# MCU.net
KiCad netlist of a schematic drawn in Altium Designer
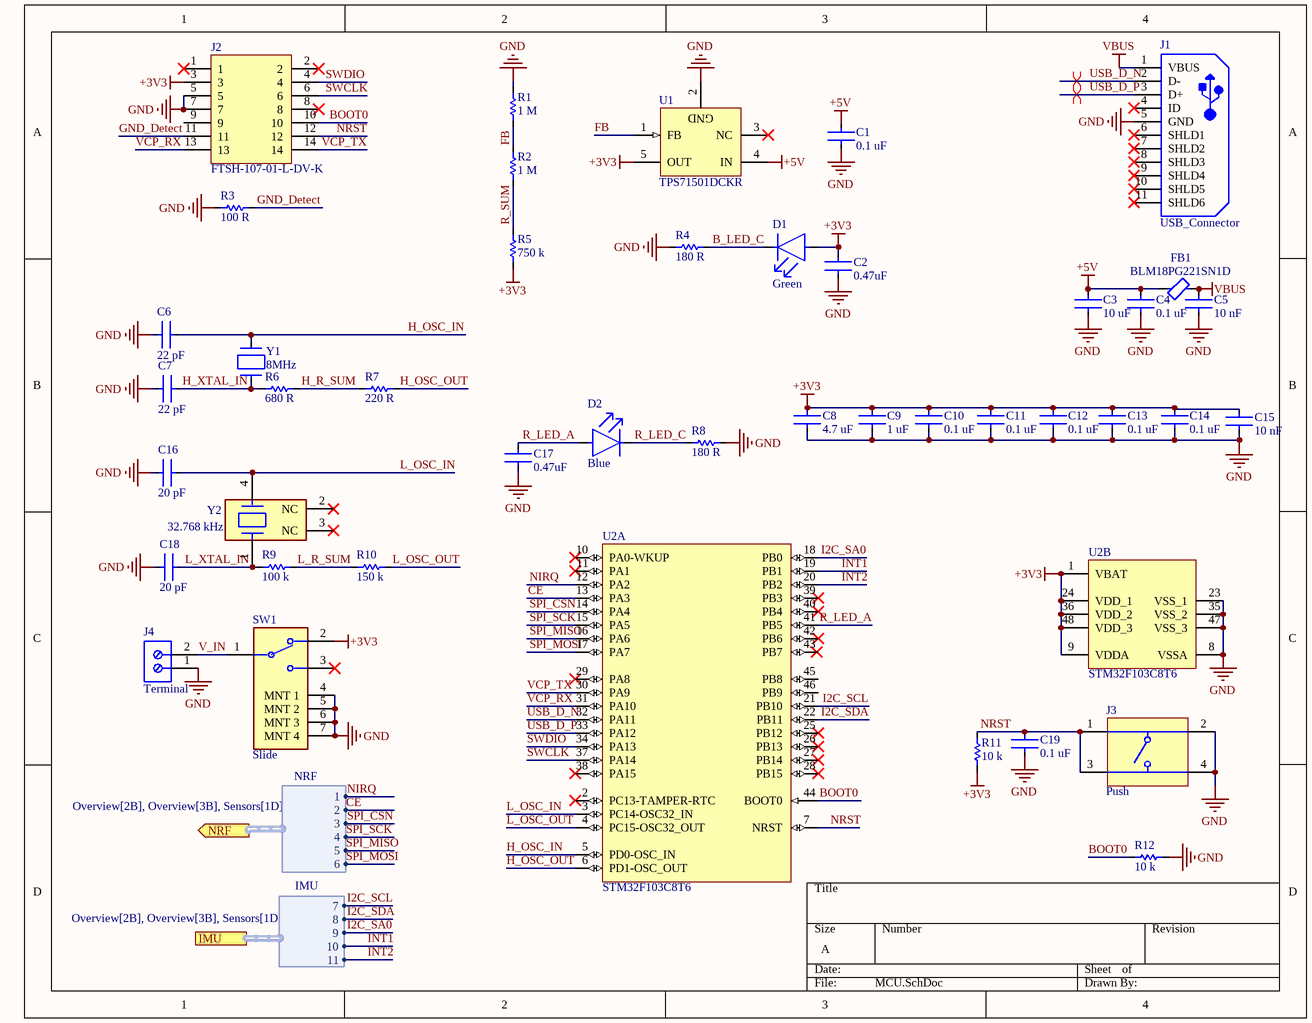
[diagram p0: MCU.SchDoc]

(export (version "E")
  (design (tool "Eeschema 10.0.6"))
  (components
    (comp (ref "C1")
      (value "0.1 uF")
      (footprint "0_1uF_0603_Capacitor")
      (fields
        (field (name "MANUFACTURER") "Murata")
        (field (name "MANUFACTURER PART NUMBER") "GCM188L81H104KA57D")
      )
      (libsource (lib "V2SchLib") (part "0_1uF_0603_Capacitor"))
    )
    (comp (ref "C2")
      (value "0.47uF")
      (footprint "0_47uF_0603_Capacitor")
      (fields
        (field (name "MANUFACTURER") "Murata")
        (field (name "MANUFACTURER PART NUMBER") "GRM188R71E474KA12D")
      )
      (libsource (lib "V2SchLib") (part "0_47uF_0603_Capacitor"))
    )
    (comp (ref "C3")
      (value "10 uF")
      (footprint "10uF_0603_Capacitor")
      (fields
        (field (name "MANUFACTURER") "Murata")
        (field (name "MANUFACTURER PART NUMBER") "GRM188R60J106KE47D")
      )
      (libsource (lib "V2SchLib") (part "10uF_0603_Capacitor"))
    )
    (comp (ref "C4")
      (value "0.1 uF")
      (footprint "0_1uF_0603_Capacitor")
      (fields
        (field (name "MANUFACTURER") "Murata")
        (field (name "MANUFACTURER PART NUMBER") "GCM188L81H104KA57D")
      )
      (libsource (lib "V2SchLib") (part "0_1uF_0603_Capacitor"))
    )
    (comp (ref "C5")
      (value "10 nF")
      (footprint "10nF_0603_Capacitor")
      (fields
        (field (name "MANUFACTURER") "Yageo")
        (field (name "MANUFACTURER PART NUMBER") "CC0603KRX7R9BB103")
      )
      (libsource (lib "V2SchLib") (part "10nF_0603_Capacitor"))
    )
    (comp (ref "C6")
      (value "22 pF")
      (footprint "22pF_0603_Capacitor")
      (fields
        (field (name "MANUFACTURER") "Murata")
        (field (name "MANUFACTURER PART NUMBER") "GCM1885C2A220JA16D")
      )
      (libsource (lib "V2SchLib") (part "22pF_0603_Capacitor"))
    )
    (comp (ref "C7")
      (value "22 pF")
      (footprint "22pF_0603_Capacitor")
      (fields
        (field (name "MANUFACTURER") "Murata")
        (field (name "MANUFACTURER PART NUMBER") "GCM1885C2A220JA16D")
      )
      (libsource (lib "V2SchLib") (part "22pF_0603_Capacitor"))
    )
    (comp (ref "C8")
      (value "4.7 uF")
      (footprint "4_7uF_0603_Capacitor")
      (fields
        (field (name "MANUFACTURER") "Murata")
        (field (name "MANUFACTURER PART NUMBER") "GRM188R61C475KAAJD")
      )
      (libsource (lib "V2SchLib") (part "4_7uF_0603_Capacitor"))
    )
    (comp (ref "C9")
      (value "1 uF")
      (footprint "1uF_0603_Capacitor")
      (fields
        (field (name "MANUFACTURER") "Yageo")
        (field (name "MANUFACTURER PART NUMBER") "CC0603KRX5R9BB105")
      )
      (libsource (lib "V2SchLib") (part "1uF_0603_Capacitor"))
    )
    (comp (ref "C10")
      (value "0.1 uF")
      (footprint "0_1uF_0603_Capacitor")
      (fields
        (field (name "MANUFACTURER") "Murata")
        (field (name "MANUFACTURER PART NUMBER") "GCM188L81H104KA57D")
      )
      (libsource (lib "V2SchLib") (part "0_1uF_0603_Capacitor"))
    )
    (comp (ref "C11")
      (value "0.1 uF")
      (footprint "0_1uF_0603_Capacitor")
      (fields
        (field (name "MANUFACTURER") "Murata")
        (field (name "MANUFACTURER PART NUMBER") "GCM188L81H104KA57D")
      )
      (libsource (lib "V2SchLib") (part "0_1uF_0603_Capacitor"))
    )
    (comp (ref "C12")
      (value "0.1 uF")
      (footprint "0_1uF_0603_Capacitor")
      (fields
        (field (name "MANUFACTURER") "Murata")
        (field (name "MANUFACTURER PART NUMBER") "GCM188L81H104KA57D")
      )
      (libsource (lib "V2SchLib") (part "0_1uF_0603_Capacitor"))
    )
    (comp (ref "C13")
      (value "0.1 uF")
      (footprint "0_1uF_0603_Capacitor")
      (fields
        (field (name "MANUFACTURER") "Murata")
        (field (name "MANUFACTURER PART NUMBER") "GCM188L81H104KA57D")
      )
      (libsource (lib "V2SchLib") (part "0_1uF_0603_Capacitor"))
    )
    (comp (ref "C14")
      (value "0.1 uF")
      (footprint "0_1uF_0603_Capacitor")
      (fields
        (field (name "MANUFACTURER") "Murata")
        (field (name "MANUFACTURER PART NUMBER") "GCM188L81H104KA57D")
      )
      (libsource (lib "V2SchLib") (part "0_1uF_0603_Capacitor"))
    )
    (comp (ref "C15")
      (value "10 nF")
      (footprint "10nF_0603_Capacitor")
      (fields
        (field (name "MANUFACTURER") "Yageo")
        (field (name "MANUFACTURER PART NUMBER") "CC0603KRX7R9BB103")
      )
      (libsource (lib "V2SchLib") (part "10nF_0603_Capacitor"))
    )
    (comp (ref "C16")
      (value "20 pF")
      (footprint "20pF_0603_Capacitor")
      (fields
        (field (name "MANUFACTURER") "Yageo")
        (field (name "MANUFACTURER PART NUMBER") "CC0603JRNPO9BN200")
      )
      (libsource (lib "V2SchLib") (part "20pF_0603_Capacitor"))
    )
    (comp (ref "C17")
      (value "0.47uF")
      (footprint "0_47uF_0603_Capacitor")
      (fields
        (field (name "MANUFACTURER") "Murata")
        (field (name "MANUFACTURER PART NUMBER") "GRM188R71E474KA12D")
      )
      (libsource (lib "V2SchLib") (part "0_47uF_0603_Capacitor"))
    )
    (comp (ref "C18")
      (value "20 pF")
      (footprint "20pF_0603_Capacitor")
      (fields
        (field (name "MANUFACTURER") "Yageo")
        (field (name "MANUFACTURER PART NUMBER") "CC0603JRNPO9BN200")
      )
      (libsource (lib "V2SchLib") (part "20pF_0603_Capacitor"))
    )
    (comp (ref "C19")
      (value "0.1 uF")
      (footprint "0_1uF_0603_Capacitor")
      (fields
        (field (name "MANUFACTURER") "Murata")
        (field (name "MANUFACTURER PART NUMBER") "GCM188L81H104KA57D")
      )
      (libsource (lib "V2SchLib") (part "0_1uF_0603_Capacitor"))
    )
    (comp (ref "D1")
      (value "Green")
      (footprint "Green_LED")
      (description "Single Color LED, Yellow Green, 1.1mm, VLMG1300-GS08")
      (fields
        (field (name "MANUFACTURER") "Vishay Semiconductors")
        (field (name "MANUFACTURER PART NUMBER") "VLMG1300-GS08")
      )
      (libsource (lib "V2SchLib") (part "Green_LED"))
    )
    (comp (ref "D2")
      (value "Blue")
      (footprint "Blue_LED")
      (description "Single Color LED, Ultra Bright Blue, Water Clear, 1.1mm, LTST-C191TBKT")
      (fields
        (field (name "MANUFACTURER") "Vishay Lite-On")
        (field (name "MANUFACTURER PART NUMBER") "LTST-C191TBKT")
      )
      (libsource (lib "V2SchLib") (part "Blue_LED"))
    )
    (comp (ref "FB1")
      (value "BLM18PG221SN1D")
      (footprint "Ferrite_Bead")
      (description "Ferrite Chip, 1 Function(s), 1.4A, 2 Pin(s), BLM18PG221SN1D")
      (fields (field (name "MANUFACTURER") "Murata"))
      (libsource (lib "V2SchLib") (part "Ferrite_Bead"))
    )
    (comp (ref "J1")
      (value "USB_Connector")
      (footprint "MICRO_USB")
      (fields (field (name "MANUFACTURER") "Molex") (field (name "MANUFACTURER PART NUMBER") "1050170001"))
      (libsource (lib "V2SchLib") (part "USB_Connector"))
    )
    (comp (ref "J2")
      (value "FTSH-107-01-L-DV-K")
      (footprint "SWD_Header_Connector")
      (fields (field (name "MANUFACTURER") "Samtec"))
      (libsource (lib "V2SchLib") (part "SWD_Header_Connector"))
    )
    (comp (ref "J3")
      (value "Push")
      (footprint "Push_Button")
      (fields
        (field (name "MANUFACTURER") "TE Connectivity Alcoswitch")
        (field (name "MANUFACTURER PART NUMBER") "1825910-6")
      )
      (libsource (lib "V2SchLib") (part "Push_Button"))
    )
    (comp (ref "J4")
      (value "Terminal")
      (footprint "Screw_Terminal")
      (description "Barrier Strip Terminal Block, 6A, 0.5mm2, 1 Row(s), 1 Deck(s), 1725656 Phoenix Contact")
      (fields
        (field (name "MANUFACTURER") "Phoenix Contact")
        (field (name "MANUFACTURER PART NUMBER") "1725656")
        (field (name "SAFETY APPROVAL") "UL,CSA,CUL,EAC")
      )
      (libsource (lib "V2SchLib") (part "Screw_Terminal"))
    )
    (comp (ref "R1")
      (value "1 M")
      (footprint "1M_0603_Resistor")
      (fields
        (field (name "MANUFACTURER") "Vishay")
        (field (name "MANUFACTURER PART NUMBER") "CRCW06031M00FKEA")
        (field (name "TOLERANCE") "1%")
      )
      (libsource (lib "V2SchLib") (part "1M_0603_Resistor"))
    )
    (comp (ref "R2")
      (value "1 M")
      (footprint "1M_0603_Resistor")
      (fields
        (field (name "MANUFACTURER") "Vishay")
        (field (name "MANUFACTURER PART NUMBER") "CRCW06031M00FKEA")
        (field (name "TOLERANCE") "1%")
      )
      (libsource (lib "V2SchLib") (part "1M_0603_Resistor"))
    )
    (comp (ref "R3")
      (value "100 R")
      (footprint "100R_0603_Resistor")
      (fields
        (field (name "MANUFACTURER") "Vishay Dale")
        (field (name "MANUFACTURER PART NUMBER") "CRCW0603100RFKEA")
        (field (name "TOLERANCE") "1%")
      )
      (libsource (lib "V2SchLib") (part "100R_0603_Resistor"))
    )
    (comp (ref "R4")
      (value "180 R")
      (footprint "180R_0603_Resistor")
      (fields
        (field (name "MANUFACTURER") "Panasonic")
        (field (name "MANUFACTURER PART NUMBER") "ERJ-3EKF1800V")
        (field (name "TOLERANCE") "1%")
      )
      (libsource (lib "V2SchLib") (part "180R_0603_Resistor"))
    )
    (comp (ref "R5")
      (value "750 k")
      (footprint "750k_0603_Resistor")
      (fields
        (field (name "MANUFACTURER") "Yageo")
        (field (name "MANUFACTURER PART NUMBER") "RC0603FR-07750KL")
        (field (name "TOLERANCE") "1%")
      )
      (libsource (lib "V2SchLib") (part "750k_0603_Resistor"))
    )
    (comp (ref "R6")
      (value "680 R")
      (footprint "680R_0603_Resistor")
      (fields
        (field (name "MANUFACTURER") "Panasonic")
        (field (name "MANUFACTURER PART NUMBER") "ERJ-3EKF6800V")
        (field (name "TOLERANCE") "1%")
      )
      (libsource (lib "V2SchLib") (part "680R_0603_Resistor"))
    )
    (comp (ref "R7")
      (value "220 R")
      (footprint "220R_0603_Resistor")
      (fields
        (field (name "MANUFACTURER") "Panasonic")
        (field (name "MANUFACTURER PART NUMBER") "ERJ-3EKF2200V")
        (field (name "TOLERANCE") "1%")
      )
      (libsource (lib "V2SchLib") (part "220R_0603_Resistor"))
    )
    (comp (ref "R8")
      (value "180 R")
      (footprint "180R_0603_Resistor")
      (fields
        (field (name "MANUFACTURER") "Panasonic")
        (field (name "MANUFACTURER PART NUMBER") "ERJ-3EKF1800V")
        (field (name "TOLERANCE") "1%")
      )
      (libsource (lib "V2SchLib") (part "180R_0603_Resistor"))
    )
    (comp (ref "R9")
      (value "100 k")
      (footprint "100k_0603_Resistor")
      (fields
        (field (name "MANUFACTURER") "Yageo")
        (field (name "MANUFACTURER PART NUMBER") "AC0603FR-07100KL")
        (field (name "TOLERANCE") "1%")
      )
      (libsource (lib "V2SchLib") (part "100k_0603_Resistor"))
    )
    (comp (ref "R10")
      (value "150 k")
      (footprint "150k_0603_Resistor")
      (fields
        (field (name "MANUFACTURER") "Yageo")
        (field (name "MANUFACTURER PART NUMBER") "RC0603FR-07150KL")
        (field (name "TOLERANCE") "1%")
      )
      (libsource (lib "V2SchLib") (part "150k_0603_Resistor"))
    )
    (comp (ref "R11")
      (value "10 k")
      (footprint "10k_0603_Resistor")
      (fields
        (field (name "MANUFACTURER") "Yageo")
        (field (name "MANUFACTURER PART NUMBER") "RT0603BRD1010KL")
        (field (name "TOLERANCE") "0.1%")
      )
      (libsource (lib "V2SchLib") (part "10k_0603_Resistor"))
    )
    (comp (ref "R12")
      (value "10 k")
      (footprint "10k_0603_Resistor")
      (fields
        (field (name "MANUFACTURER") "Yageo")
        (field (name "MANUFACTURER PART NUMBER") "RT0603BRD1010KL")
        (field (name "TOLERANCE") "0.1%")
      )
      (libsource (lib "V2SchLib") (part "10k_0603_Resistor"))
    )
    (comp (ref "SW1")
      (value "Slide")
      (footprint "Slide_Switch")
      (description "Slide Switch, SPDT, Latched, 0.3A, 6VDC, Solder Terminal, Surface Mount-right Angle, PCM12SMTR")
      (fields (field (name "MANUFACTURER") "ITT C&K") (field (name "MANUFACTURER PART NUMBER") "PCM12SMTR"))
      (libsource (lib "V2SchLib") (part "Slide_Switch"))
    )
    (comp (ref "U1")
      (value "TPS71501DCKR")
      (footprint "5V_3V3_LDO")
      (fields
        (field (name "MANUFACTURER") "Texas Instruments")
        (field (name "MANUFACTURER PART NUMBER") "TPS71533DCKR")
      )
      (libsource (lib "V2SchLib") (part "5V_3V3_LDO"))
    )
    (comp (ref "U2")
      (value "STM32F103C8T6")
      (footprint "STM32")
      (description "RISC Microcontroller, 32-Bit, FLASH, STM32 CPU, 72MHz, CMOS, PQFP48, STM32F103C8T6")
      (fields
        (field (name "MANUFACTURER") "STMicroelectronics")
        (field (name "MANUFACTURER PART NUMBER") "STM32C011F4U6TR")
      )
      (libsource (lib "V2SchLib") (part "STM32F103C8T6"))
    )
    (comp (ref "Y1")
      (value "8MHz")
      (footprint "8MHz_Oscillator")
      (fields
        (field (name "MANUFACTURER") "Abracon")
        (field (name "MANUFACTURER PART NUMBER") "ABM7-8.000MHZ-D2Y-T")
      )
      (libsource (lib "V2SchLib") (part "8MHz_Oscillator"))
    )
    (comp (ref "Y2")
      (value "32.768 kHz")
      (footprint "32_768MHz_Oscillator")
      (description "Parallel - Fundamental Quartz Crystal, 0.032768MHz Nom, ABS25-32.768KHZ-T")
      (fields
        (field (name "MANUFACTURER") "Abracon")
        (field (name "MANUFACTURER PART NUMBER") "ABS25-32.768KHZ-T")
      )
      (libsource (lib "V2SchLib") (part "32_768kHz_Oscillator"))
    )
  )
  (nets
    (net (code "3") (name "+3V3") (class "Default")
      (node (ref "C10") (pin "1") (pinfunction "1_1") (pintype "passive"))
      (node (ref "C11") (pin "1") (pinfunction "1_1") (pintype "passive"))
      (node (ref "C12") (pin "1") (pinfunction "1_1") (pintype "passive"))
      (node (ref "C13") (pin "1") (pinfunction "1_1") (pintype "passive"))
      (node (ref "C14") (pin "1") (pinfunction "1_1") (pintype "passive"))
      (node (ref "C15") (pin "1") (pinfunction "1_1") (pintype "passive"))
      (node (ref "C2") (pin "1") (pinfunction "1_1") (pintype "passive"))
      (node (ref "C8") (pin "1") (pinfunction "1_1") (pintype "passive"))
      (node (ref "C9") (pin "1") (pinfunction "1_1") (pintype "passive"))
      (node (ref "D1") (pin "2") (pinfunction "A_2") (pintype "passive"))
      (node (ref "J2") (pin "3") (pinfunction "3_3") (pintype "passive"))
      (node (ref "R11") (pin "1") (pinfunction "1_1") (pintype "passive"))
      (node (ref "R5") (pin "1") (pinfunction "1_1") (pintype "passive"))
      (node (ref "SW1") (pin "2") (pinfunction "2_2") (pintype "passive"))
      (node (ref "U1") (pin "5") (pinfunction "OUT_5") (pintype "power_in"))
      (node (ref "U2") (pin "1") (pinfunction "VBAT_1") (pintype "passive"))
      (node (ref "U2") (pin "24") (pinfunction "VDD_1_24") (pintype "passive"))
      (node (ref "U2") (pin "36") (pinfunction "VDD_2_36") (pintype "passive"))
      (node (ref "U2") (pin "48") (pinfunction "VDD_3_48") (pintype "passive"))
      (node (ref "U2") (pin "9") (pinfunction "VDDA_9") (pintype "passive"))
    )
    (net (code "4") (name "+5V") (class "Default")
      (node (ref "C1") (pin "1") (pinfunction "1_1") (pintype "passive"))
      (node (ref "C3") (pin "1") (pinfunction "1_1") (pintype "passive"))
      (node (ref "C4") (pin "1") (pinfunction "1_1") (pintype "passive"))
      (node (ref "FB1") (pin "1") (pinfunction "1_1") (pintype "passive"))
      (node (ref "U1") (pin "4") (pinfunction "IN_4") (pintype "power_in"))
    )
    (net (code "5") (name "/BOOT0") (class "Default")
      (node (ref "J2") (pin "10") (pinfunction "10_10") (pintype "passive"))
      (node (ref "R12") (pin "2") (pinfunction "2_2") (pintype "passive"))
      (node (ref "U2") (pin "44") (pinfunction "BOOT0_44") (pintype "input"))
    )
    (net (code "6") (name "/B_LED_C") (class "Default")
      (node (ref "D1") (pin "1") (pinfunction "C_1") (pintype "passive"))
      (node (ref "R4") (pin "2") (pinfunction "2_2") (pintype "passive"))
    )
    (net (code "7") (name "/CE") (class "Default")
      (node (ref "U2") (pin "13") (pinfunction "PA3_13") (pintype "bidirectional"))
    )
    (net (code "8") (name "/FB") (class "Default")
      (node (ref "R1") (pin "1") (pinfunction "1_1") (pintype "passive"))
      (node (ref "R2") (pin "2") (pinfunction "2_2") (pintype "passive"))
      (node (ref "U1") (pin "1") (pinfunction "FB_1") (pintype "input"))
    )
    (net (code "9") (name "/GND_Detect") (class "Default")
      (node (ref "J2") (pin "11") (pinfunction "11_11") (pintype "passive"))
      (node (ref "R3") (pin "2") (pinfunction "2_2") (pintype "passive"))
    )
    (net (code "10") (name "/H_OSC_IN") (class "Default")
      (node (ref "C6") (pin "1") (pinfunction "1_1") (pintype "passive"))
      (node (ref "U2") (pin "5") (pinfunction "PD0-OSC_IN_5") (pintype "bidirectional"))
      (node (ref "Y1") (pin "2") (pinfunction "2_2") (pintype "passive"))
    )
    (net (code "11") (name "/H_OSC_OUT") (class "Default")
      (node (ref "R7") (pin "2") (pinfunction "2_2") (pintype "passive"))
      (node (ref "U2") (pin "6") (pinfunction "PD1-OSC_OUT_6") (pintype "bidirectional"))
    )
    (net (code "12") (name "/H_R_SUM") (class "Default")
      (node (ref "R6") (pin "2") (pinfunction "2_2") (pintype "passive"))
      (node (ref "R7") (pin "1") (pinfunction "1_1") (pintype "passive"))
    )
    (net (code "13") (name "/H_XTAL_IN") (class "Default")
      (node (ref "C7") (pin "1") (pinfunction "1_1") (pintype "passive"))
      (node (ref "R6") (pin "1") (pinfunction "1_1") (pintype "passive"))
      (node (ref "Y1") (pin "1") (pinfunction "1_1") (pintype "passive"))
    )
    (net (code "14") (name "/I2C_SA0") (class "Default")
      (node (ref "U2") (pin "18") (pinfunction "PB0_18") (pintype "bidirectional"))
    )
    (net (code "15") (name "/I2C_SCL") (class "Default")
      (node (ref "U2") (pin "21") (pinfunction "PB10_21") (pintype "bidirectional"))
    )
    (net (code "16") (name "/I2C_SDA") (class "Default")
      (node (ref "U2") (pin "22") (pinfunction "PB11_22") (pintype "bidirectional"))
    )
    (net (code "17") (name "/INT1") (class "Default")
      (node (ref "U2") (pin "19") (pinfunction "PB1_19") (pintype "bidirectional"))
    )
    (net (code "18") (name "/INT2") (class "Default")
      (node (ref "U2") (pin "20") (pinfunction "PB2_20") (pintype "bidirectional"))
    )
    (net (code "19") (name "/L_OSC_IN") (class "Default")
      (node (ref "C16") (pin "1") (pinfunction "1_1") (pintype "passive"))
      (node (ref "U2") (pin "3") (pinfunction "PC14-OSC32_IN_3") (pintype "bidirectional"))
      (node (ref "Y2") (pin "4") (pinfunction "4_4") (pintype "passive"))
    )
    (net (code "20") (name "/L_OSC_OUT") (class "Default")
      (node (ref "R10") (pin "2") (pinfunction "2_2") (pintype "passive"))
      (node (ref "U2") (pin "4") (pinfunction "PC15-OSC32_OUT_4") (pintype "bidirectional"))
    )
    (net (code "21") (name "/L_R_SUM") (class "Default")
      (node (ref "R10") (pin "1") (pinfunction "1_1") (pintype "passive"))
      (node (ref "R9") (pin "2") (pinfunction "2_2") (pintype "passive"))
    )
    (net (code "22") (name "/L_XTAL_IN") (class "Default")
      (node (ref "C18") (pin "1") (pinfunction "1_1") (pintype "passive"))
      (node (ref "R9") (pin "1") (pinfunction "1_1") (pintype "passive"))
      (node (ref "Y2") (pin "1") (pinfunction "1_1") (pintype "passive"))
    )
    (net (code "23") (name "/NIRQ") (class "Default")
      (node (ref "U2") (pin "12") (pinfunction "PA2_12") (pintype "bidirectional"))
    )
    (net (code "24") (name "/NRST") (class "Default")
      (node (ref "C19") (pin "1") (pinfunction "1_1") (pintype "passive"))
      (node (ref "J2") (pin "12") (pinfunction "12_12") (pintype "passive"))
      (node (ref "J3") (pin "1") (pinfunction "1_1") (pintype "passive"))
      (node (ref "J3") (pin "3") (pinfunction "3_3") (pintype "passive"))
      (node (ref "R11") (pin "2") (pinfunction "2_2") (pintype "passive"))
      (node (ref "U2") (pin "7") (pinfunction "NRST_7") (pintype "bidirectional"))
    )
    (net (code "25") (name "/R_LED_A") (class "Default")
      (node (ref "C17") (pin "1") (pinfunction "1_1") (pintype "passive"))
      (node (ref "D2") (pin "2") (pinfunction "A_2") (pintype "passive"))
      (node (ref "U2") (pin "41") (pinfunction "PB5_41") (pintype "bidirectional"))
    )
    (net (code "26") (name "/R_LED_C") (class "Default")
      (node (ref "D2") (pin "1") (pinfunction "C_1") (pintype "passive"))
      (node (ref "R8") (pin "1") (pinfunction "1_1") (pintype "passive"))
    )
    (net (code "27") (name "/R_SUM") (class "Default")
      (node (ref "R2") (pin "1") (pinfunction "1_1") (pintype "passive"))
      (node (ref "R5") (pin "2") (pinfunction "2_2") (pintype "passive"))
    )
    (net (code "28") (name "/SPI_CSN") (class "Default")
      (node (ref "U2") (pin "14") (pinfunction "PA4_14") (pintype "bidirectional"))
    )
    (net (code "29") (name "/SPI_MISO") (class "Default")
      (node (ref "U2") (pin "16") (pinfunction "PA6_16") (pintype "bidirectional"))
    )
    (net (code "30") (name "/SPI_MOSI") (class "Default")
      (node (ref "U2") (pin "17") (pinfunction "PA7_17") (pintype "bidirectional"))
    )
    (net (code "31") (name "/SPI_SCK") (class "Default")
      (node (ref "U2") (pin "15") (pinfunction "PA5_15") (pintype "bidirectional"))
    )
    (net (code "32") (name "/SWCLK") (class "Default")
      (node (ref "J2") (pin "6") (pinfunction "6_6") (pintype "passive"))
      (node (ref "U2") (pin "37") (pinfunction "PA14_37") (pintype "bidirectional"))
    )
    (net (code "33") (name "/SWDIO") (class "Default")
      (node (ref "J2") (pin "4") (pinfunction "4_4") (pintype "passive"))
      (node (ref "U2") (pin "34") (pinfunction "PA13_34") (pintype "bidirectional"))
    )
    (net (code "34") (name "/USB_D_N") (class "Default")
      (node (ref "J1") (pin "2") (pinfunction "D-_2") (pintype "passive"))
      (node (ref "U2") (pin "32") (pinfunction "PA11_32") (pintype "bidirectional"))
    )
    (net (code "35") (name "/USB_D_P") (class "Default")
      (node (ref "J1") (pin "3") (pinfunction "D+_3") (pintype "passive"))
      (node (ref "U2") (pin "33") (pinfunction "PA12_33") (pintype "bidirectional"))
    )
    (net (code "36") (name "/VCP_RX") (class "Default")
      (node (ref "J2") (pin "13") (pinfunction "13_13") (pintype "passive"))
      (node (ref "U2") (pin "31") (pinfunction "PA10_31") (pintype "bidirectional"))
    )
    (net (code "37") (name "/VCP_TX") (class "Default")
      (node (ref "J2") (pin "14") (pinfunction "14_14") (pintype "passive"))
      (node (ref "U2") (pin "30") (pinfunction "PA9_30") (pintype "bidirectional"))
    )
    (net (code "38") (name "/V_IN") (class "Default")
      (node (ref "J4") (pin "2") (pinfunction "2_2") (pintype "passive"))
      (node (ref "SW1") (pin "1") (pinfunction "1_1") (pintype "passive"))
    )
    (net (code "41") (name "GND") (class "Default")
      (node (ref "C1") (pin "2") (pinfunction "2_2") (pintype "passive"))
      (node (ref "C10") (pin "2") (pinfunction "2_2") (pintype "passive"))
      (node (ref "C11") (pin "2") (pinfunction "2_2") (pintype "passive"))
      (node (ref "C12") (pin "2") (pinfunction "2_2") (pintype "passive"))
      (node (ref "C13") (pin "2") (pinfunction "2_2") (pintype "passive"))
      (node (ref "C14") (pin "2") (pinfunction "2_2") (pintype "passive"))
      (node (ref "C15") (pin "2") (pinfunction "2_2") (pintype "passive"))
      (node (ref "C16") (pin "2") (pinfunction "2_2") (pintype "passive"))
      (node (ref "C17") (pin "2") (pinfunction "2_2") (pintype "passive"))
      (node (ref "C18") (pin "2") (pinfunction "2_2") (pintype "passive"))
      (node (ref "C19") (pin "2") (pinfunction "2_2") (pintype "passive"))
      (node (ref "C2") (pin "2") (pinfunction "2_2") (pintype "passive"))
      (node (ref "C3") (pin "2") (pinfunction "2_2") (pintype "passive"))
      (node (ref "C4") (pin "2") (pinfunction "2_2") (pintype "passive"))
      (node (ref "C5") (pin "2") (pinfunction "2_2") (pintype "passive"))
      (node (ref "C6") (pin "2") (pinfunction "2_2") (pintype "passive"))
      (node (ref "C7") (pin "2") (pinfunction "2_2") (pintype "passive"))
      (node (ref "C8") (pin "2") (pinfunction "2_2") (pintype "passive"))
      (node (ref "C9") (pin "2") (pinfunction "2_2") (pintype "passive"))
      (node (ref "J1") (pin "5") (pinfunction "GND_5") (pintype "passive"))
      (node (ref "J2") (pin "5") (pinfunction "5_5") (pintype "passive"))
      (node (ref "J2") (pin "7") (pinfunction "7_7") (pintype "passive"))
      (node (ref "J3") (pin "2") (pinfunction "2_2") (pintype "passive"))
      (node (ref "J3") (pin "4") (pinfunction "4_4") (pintype "passive"))
      (node (ref "J4") (pin "1") (pinfunction "1_1") (pintype "passive"))
      (node (ref "R1") (pin "2") (pinfunction "2_2") (pintype "passive"))
      (node (ref "R12") (pin "1") (pinfunction "1_1") (pintype "passive"))
      (node (ref "R3") (pin "1") (pinfunction "1_1") (pintype "passive"))
      (node (ref "R4") (pin "1") (pinfunction "1_1") (pintype "passive"))
      (node (ref "R8") (pin "2") (pinfunction "2_2") (pintype "passive"))
      (node (ref "SW1") (pin "4") (pinfunction "MNT_1_4") (pintype "passive"))
      (node (ref "SW1") (pin "5") (pinfunction "MNT_2_5") (pintype "passive"))
      (node (ref "SW1") (pin "6") (pinfunction "MNT_3_6") (pintype "passive"))
      (node (ref "SW1") (pin "7") (pinfunction "MNT_4_7") (pintype "passive"))
      (node (ref "U1") (pin "2") (pinfunction "GND_2") (pintype "power_in"))
      (node (ref "U2") (pin "23") (pinfunction "VSS_1_23") (pintype "passive"))
      (node (ref "U2") (pin "35") (pinfunction "VSS_2_35") (pintype "passive"))
      (node (ref "U2") (pin "47") (pinfunction "VSS_3_47") (pintype "passive"))
      (node (ref "U2") (pin "8") (pinfunction "VSSA_8") (pintype "passive"))
    )
    (net (code "42") (name "VBUS") (class "Default")
      (node (ref "C5") (pin "1") (pinfunction "1_1") (pintype "passive"))
      (node (ref "FB1") (pin "2") (pinfunction "2_2") (pintype "passive"))
      (node (ref "J1") (pin "1") (pinfunction "VBUS_1") (pintype "passive"))
    )
    (net (code "43") (name "unconnected-(J1-ID-Pad4)") (class "Default")
      (node (ref "J1") (pin "4") (pinfunction "ID_4") (pintype "passive+no_connect"))
    )
    (net (code "44") (name "unconnected-(J1-SHLD1-Pad6)") (class "Default")
      (node (ref "J1") (pin "6") (pinfunction "SHLD1_6") (pintype "passive+no_connect"))
    )
    (net (code "45") (name "unconnected-(J1-SHLD2-Pad7)") (class "Default")
      (node (ref "J1") (pin "7") (pinfunction "SHLD2_7") (pintype "passive+no_connect"))
    )
    (net (code "46") (name "unconnected-(J1-SHLD3-Pad8)") (class "Default")
      (node (ref "J1") (pin "8") (pinfunction "SHLD3_8") (pintype "passive+no_connect"))
    )
    (net (code "47") (name "unconnected-(J1-SHLD4-Pad9)") (class "Default")
      (node (ref "J1") (pin "9") (pinfunction "SHLD4_9") (pintype "passive+no_connect"))
    )
    (net (code "48") (name "unconnected-(J1-SHLD5-Pad10)") (class "Default")
      (node (ref "J1") (pin "10") (pinfunction "SHLD5_10") (pintype "passive+no_connect"))
    )
    (net (code "49") (name "unconnected-(J1-SHLD6-Pad11)") (class "Default")
      (node (ref "J1") (pin "11") (pinfunction "SHLD6_11") (pintype "passive+no_connect"))
    )
    (net (code "50") (name "unconnected-(J2-Pad1)") (class "Default")
      (node (ref "J2") (pin "1") (pinfunction "1_1") (pintype "passive+no_connect"))
    )
    (net (code "51") (name "unconnected-(J2-Pad2)") (class "Default")
      (node (ref "J2") (pin "2") (pinfunction "2_2") (pintype "passive+no_connect"))
    )
    (net (code "52") (name "unconnected-(J2-Pad8)") (class "Default")
      (node (ref "J2") (pin "8") (pinfunction "8_8") (pintype "passive+no_connect"))
    )
    (net (code "53") (name "unconnected-(J2-Pad9)") (class "Default")
      (node (ref "J2") (pin "9") (pinfunction "9_9") (pintype "passive"))
    )
    (net (code "54") (name "unconnected-(SW1-Pad3)") (class "Default")
      (node (ref "SW1") (pin "3") (pinfunction "3_3") (pintype "passive+no_connect"))
    )
    (net (code "55") (name "unconnected-(U1-NC-Pad3)") (class "Default")
      (node (ref "U1") (pin "3") (pinfunction "NC_3") (pintype "passive+no_connect"))
    )
    (net (code "56") (name "unconnected-(U2A-PA0-WKUP-Pad10)") (class "Default")
      (node (ref "U2") (pin "10") (pinfunction "PA0-WKUP_10") (pintype "bidirectional+no_connect"))
    )
    (net (code "57") (name "unconnected-(U2A-PA1-Pad11)") (class "Default")
      (node (ref "U2") (pin "11") (pinfunction "PA1_11") (pintype "bidirectional+no_connect"))
    )
    (net (code "58") (name "unconnected-(U2A-PA8-Pad29)") (class "Default")
      (node (ref "U2") (pin "29") (pinfunction "PA8_29") (pintype "bidirectional+no_connect"))
    )
    (net (code "59") (name "unconnected-(U2A-PA15-Pad38)") (class "Default")
      (node (ref "U2") (pin "38") (pinfunction "PA15_38") (pintype "bidirectional+no_connect"))
    )
    (net (code "60") (name "unconnected-(U2A-PB3-Pad39)") (class "Default")
      (node (ref "U2") (pin "39") (pinfunction "PB3_39") (pintype "bidirectional+no_connect"))
    )
    (net (code "61") (name "unconnected-(U2A-PB4-Pad40)") (class "Default")
      (node (ref "U2") (pin "40") (pinfunction "PB4_40") (pintype "bidirectional+no_connect"))
    )
    (net (code "62") (name "unconnected-(U2A-PB6-Pad42)") (class "Default")
      (node (ref "U2") (pin "42") (pinfunction "PB6_42") (pintype "bidirectional+no_connect"))
    )
    (net (code "63") (name "unconnected-(U2A-PB7-Pad43)") (class "Default")
      (node (ref "U2") (pin "43") (pinfunction "PB7_43") (pintype "bidirectional"))
    )
    (net (code "64") (name "unconnected-(U2A-PB8-Pad45)") (class "Default")
      (node (ref "U2") (pin "45") (pinfunction "PB8_45") (pintype "bidirectional"))
    )
    (net (code "65") (name "unconnected-(U2A-PB9-Pad46)") (class "Default")
      (node (ref "U2") (pin "46") (pinfunction "PB9_46") (pintype "bidirectional"))
    )
    (net (code "66") (name "unconnected-(U2A-PB12-Pad25)") (class "Default")
      (node (ref "U2") (pin "25") (pinfunction "PB12_25") (pintype "bidirectional+no_connect"))
    )
    (net (code "67") (name "unconnected-(U2A-PB13-Pad26)") (class "Default")
      (node (ref "U2") (pin "26") (pinfunction "PB13_26") (pintype "bidirectional+no_connect"))
    )
    (net (code "68") (name "unconnected-(U2A-PB14-Pad27)") (class "Default")
      (node (ref "U2") (pin "27") (pinfunction "PB14_27") (pintype "bidirectional+no_connect"))
    )
    (net (code "69") (name "unconnected-(U2A-PB15-Pad28)") (class "Default")
      (node (ref "U2") (pin "28") (pinfunction "PB15_28") (pintype "bidirectional+no_connect"))
    )
    (net (code "70") (name "unconnected-(U2A-PC13-TAMPER-RTC-Pad2)") (class "Default")
      (node (ref "U2") (pin "2") (pinfunction "PC13-TAMPER-RTC_2") (pintype "bidirectional+no_connect"))
    )
    (net (code "71") (name "unconnected-(Y2-NC-Pad2)") (class "Default")
      (node (ref "Y2") (pin "2") (pinfunction "NC_2") (pintype "passive+no_connect"))
    )
    (net (code "72") (name "unconnected-(Y2-NC-Pad3)") (class "Default")
      (node (ref "Y2") (pin "3") (pinfunction "NC_3") (pintype "passive+no_connect"))
    )
  )
)
